# Automotive_Car_Cover_with_anti-theft_ale.net
KiCad netlist of a schematic drawn in EAGLE
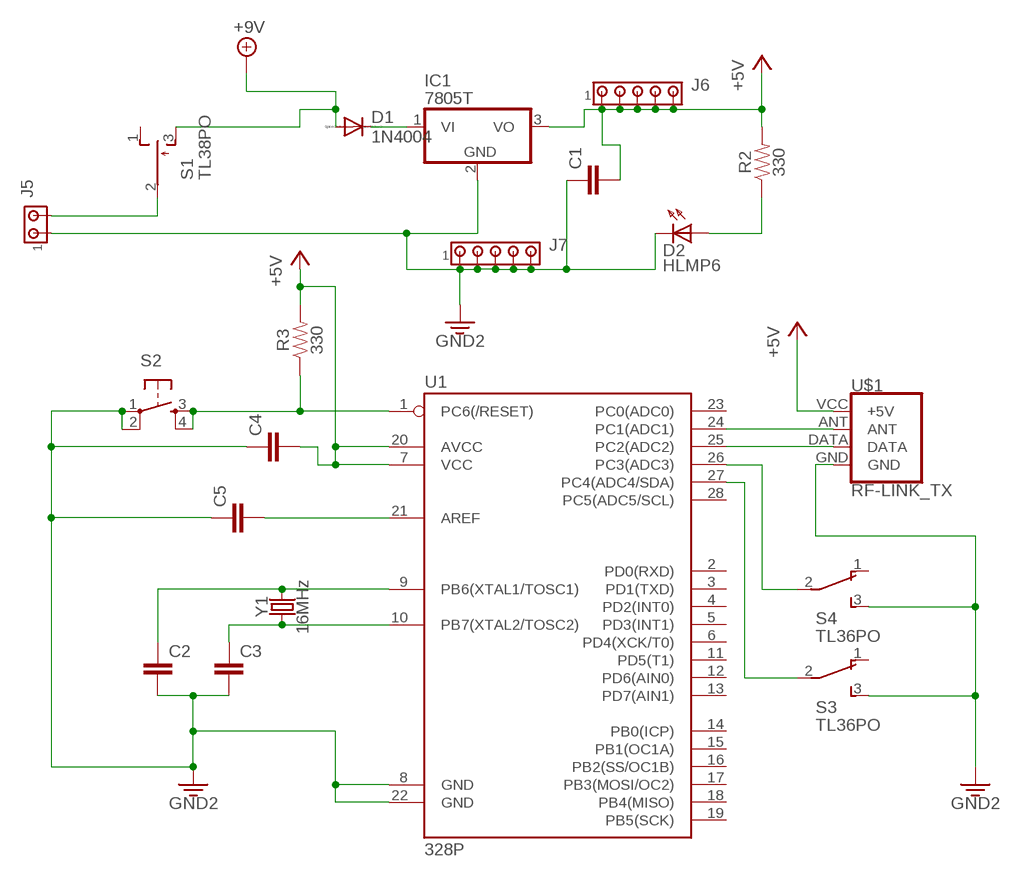
[diagram p0: schematic, sheet 1]

(export (version "E")
  (design (tool "Eeschema 10.0.6"))
  (components
    (comp (ref "C1")
      (value "C5/2.5")
      (footprint "eagle-import:C5B2.5")
      (libsource (lib "eagle-import") (part "C5/2.5"))
    )
    (comp (ref "C2")
      (value "C5/2.5")
      (footprint "eagle-import:C5B2.5")
      (libsource (lib "eagle-import") (part "C5/2.5"))
    )
    (comp (ref "C3")
      (value "C5/2.5")
      (footprint "eagle-import:C5B2.5")
      (libsource (lib "eagle-import") (part "C5/2.5"))
    )
    (comp (ref "C4")
      (value "C5/2.5")
      (footprint "eagle-import:C5B2.5")
      (libsource (lib "eagle-import") (part "C5/2.5"))
    )
    (comp (ref "C5")
      (value "C5/2.5")
      (footprint "eagle-import:C5B2.5")
      (libsource (lib "eagle-import") (part "C5/2.5"))
    )
    (comp (ref "D1")
      (value "1N4004")
      (footprint "eagle-import:DO41-10")
      (libsource (lib "eagle-import") (part "1N4004"))
    )
    (comp (ref "D2")
      (value "HLMP6")
      (footprint "eagle-import:HLMP6")
      (fields (field (name "MF") "AGILENT TECHNOLOGIES") (field (name "MPN") "HLMP-6500"))
      (libsource (lib "eagle-import") (part "HLMP6"))
    )
    (comp (ref "IC1")
      (value "7805T")
      (footprint "eagle-import:TO220H")
      (libsource (lib "eagle-import") (part "78T05"))
    )
    (comp (ref "J5")
      (value "MTA02-156")
      (footprint "eagle-import:1X2MTA")
      (libsource (lib "eagle-import") (part "MTA02-156"))
    )
    (comp (ref "J6")
      (value "MTA05-100")
      (footprint "eagle-import:10X05MTA")
      (libsource (lib "eagle-import") (part "MTA05-100"))
    )
    (comp (ref "J7")
      (value "MTA05-100")
      (footprint "eagle-import:10X05MTA")
      (libsource (lib "eagle-import") (part "MTA05-100"))
    )
    (comp (ref "R2")
      (value "330")
      (footprint "eagle-import:AXIAL-0.3")
      (libsource (lib "eagle-import") (part "330OHM-HORIZ-1/10W-5%"))
    )
    (comp (ref "R3")
      (value "330")
      (footprint "eagle-import:AXIAL-0.3")
      (libsource (lib "eagle-import") (part "330OHM-HORIZ-1/10W-5%"))
    )
    (comp (ref "S1")
      (value "TL38PO")
      (footprint "eagle-import:TL3XPO")
      (libsource (lib "eagle-import") (part "TL38PO"))
    )
    (comp (ref "S2")
      (value "TAC_SWITCHPTH")
      (footprint "eagle-import:TACTILE-PTH")
      (libsource (lib "eagle-import") (part "TAC_SWITCHPTH"))
    )
    (comp (ref "S3")
      (value "TL36PO")
      (footprint "eagle-import:TL3XPO")
      (libsource (lib "eagle-import") (part "TL36PO"))
    )
    (comp (ref "S4")
      (value "TL36PO")
      (footprint "eagle-import:TL3XPO")
      (libsource (lib "eagle-import") (part "TL36PO"))
    )
    (comp (ref "U$1")
      (value "RF-LINK_TX")
      (footprint "eagle-import:RF-LINK_TX")
      (libsource (lib "eagle-import") (part "RF-LINK_TX"))
    )
    (comp (ref "U1")
      (value "328P")
      (footprint "eagle-import:DIP28")
      (libsource (lib "eagle-import") (part "ATMEGA328P_PDIP"))
    )
    (comp (ref "Y1")
      (value "16MHz")
      (footprint "eagle-import:HC49US")
      (libsource (lib "eagle-import") (part "CRYSTAL-16MHZPTH-HC49US"))
    )
  )
  (nets
    (net (code "1") (name "+5V") (class "Default")
      (node (ref "C1") (pin "2") (pinfunction "2_2") (pintype "passive"))
      (node (ref "C4") (pin "2") (pinfunction "2_2") (pintype "passive"))
      (node (ref "IC1") (pin "3") (pinfunction "VO_3") (pintype "passive"))
      (node (ref "J6") (pin "1") (pinfunction "1_1") (pintype "passive"))
      (node (ref "J6") (pin "2") (pinfunction "2_2") (pintype "passive"))
      (node (ref "J6") (pin "3") (pinfunction "3_3") (pintype "passive"))
      (node (ref "J6") (pin "4") (pinfunction "4_4") (pintype "passive"))
      (node (ref "J6") (pin "5") (pinfunction "5_5") (pintype "passive"))
      (node (ref "R2") (pin "P$2") (pinfunction "2_P$2") (pintype "passive"))
      (node (ref "R3") (pin "P$2") (pinfunction "2_P$2") (pintype "passive"))
      (node (ref "U$1") (pin "VCC") (pinfunction "+5V_VCC") (pintype "power_in"))
      (node (ref "U1") (pin "20") (pinfunction "AVCC_20") (pintype "bidirectional"))
      (node (ref "U1") (pin "7") (pinfunction "VCC_7") (pintype "bidirectional"))
    )
    (net (code "2") (name "+9V") (class "Default")
      (node (ref "D1") (pin "A") (pinfunction "A_A") (pintype "passive"))
      (node (ref "S1") (pin "3") (pinfunction "S_3") (pintype "passive"))
    )
    (net (code "3") (name "GND2") (class "Default")
      (node (ref "C1") (pin "1") (pinfunction "1_1") (pintype "passive"))
      (node (ref "C2") (pin "2") (pinfunction "2_2") (pintype "passive"))
      (node (ref "C3") (pin "2") (pinfunction "2_2") (pintype "passive"))
      (node (ref "C4") (pin "1") (pinfunction "1_1") (pintype "passive"))
      (node (ref "C5") (pin "1") (pinfunction "1_1") (pintype "passive"))
      (node (ref "D2") (pin "K") (pinfunction "K_K") (pintype "passive"))
      (node (ref "IC1") (pin "2") (pinfunction "GND_2") (pintype "passive"))
      (node (ref "J5") (pin "1") (pinfunction "1_1") (pintype "passive"))
      (node (ref "J7") (pin "1") (pinfunction "1_1") (pintype "passive"))
      (node (ref "J7") (pin "2") (pinfunction "2_2") (pintype "passive"))
      (node (ref "J7") (pin "3") (pinfunction "3_3") (pintype "passive"))
      (node (ref "J7") (pin "4") (pinfunction "4_4") (pintype "passive"))
      (node (ref "J7") (pin "5") (pinfunction "5_5") (pintype "passive"))
      (node (ref "S2") (pin "1") (pinfunction "1_1") (pintype "passive"))
      (node (ref "S2") (pin "2") (pinfunction "2_2") (pintype "passive"))
      (node (ref "S3") (pin "3") (pinfunction "S_3") (pintype "passive"))
      (node (ref "S4") (pin "3") (pinfunction "S_3") (pintype "passive"))
      (node (ref "U$1") (pin "GND") (pinfunction "GND_GND") (pintype "power_in"))
      (node (ref "U1") (pin "22") (pinfunction "GND_22") (pintype "bidirectional"))
      (node (ref "U1") (pin "8") (pinfunction "GND_8") (pintype "bidirectional"))
    )
    (net (code "4") (name "Net-(IC1-VI)") (class "Default")
      (node (ref "D1") (pin "C") (pinfunction "C_C") (pintype "passive"))
      (node (ref "IC1") (pin "1") (pinfunction "VI_1") (pintype "input"))
    )
    (net (code "5") (name "Net-(R2-1)") (class "Default")
      (node (ref "D2") (pin "A") (pinfunction "A_A") (pintype "passive"))
      (node (ref "R2") (pin "P$1") (pinfunction "1_P$1") (pintype "passive"))
    )
    (net (code "6") (name "Net-(R3-1)") (class "Default")
      (node (ref "R3") (pin "P$1") (pinfunction "1_P$1") (pintype "passive"))
      (node (ref "S2") (pin "3") (pinfunction "3_3") (pintype "passive"))
      (node (ref "S2") (pin "4") (pinfunction "4_4") (pintype "passive"))
      (node (ref "U1") (pin "1") (pinfunction "PC6(/RESET)_1") (pintype "bidirectional"))
    )
    (net (code "7") (name "Net-(S1-P)") (class "Default")
      (node (ref "J5") (pin "2") (pinfunction "2_2") (pintype "passive"))
      (node (ref "S1") (pin "2") (pinfunction "P_2") (pintype "passive"))
    )
    (net (code "8") (name "Net-(S3-P)") (class "Default")
      (node (ref "S3") (pin "2") (pinfunction "P_2") (pintype "passive"))
      (node (ref "U1") (pin "27") (pinfunction "PC4(ADC4/SDA)_27") (pintype "bidirectional"))
    )
    (net (code "9") (name "Net-(S4-P)") (class "Default")
      (node (ref "S4") (pin "2") (pinfunction "P_2") (pintype "passive"))
      (node (ref "U1") (pin "26") (pinfunction "PC3(ADC3)_26") (pintype "bidirectional"))
    )
    (net (code "10") (name "Net-(U1-AREF)") (class "Default")
      (node (ref "C5") (pin "2") (pinfunction "2_2") (pintype "passive"))
      (node (ref "U1") (pin "21") (pinfunction "AREF_21") (pintype "bidirectional"))
    )
    (net (code "11") (name "Net-(U1-PB6(XTAL1{slash}TOSC1))") (class "Default")
      (node (ref "C2") (pin "1") (pinfunction "1_1") (pintype "passive"))
      (node (ref "U1") (pin "9") (pinfunction "PB6(XTAL1/TOSC1)_9") (pintype "bidirectional"))
      (node (ref "Y1") (pin "2") (pinfunction "2_2") (pintype "passive"))
    )
    (net (code "12") (name "Net-(U1-PB7(XTAL2{slash}TOSC2))") (class "Default")
      (node (ref "C3") (pin "1") (pinfunction "1_1") (pintype "passive"))
      (node (ref "U1") (pin "10") (pinfunction "PB7(XTAL2/TOSC2)_10") (pintype "bidirectional"))
      (node (ref "Y1") (pin "1") (pinfunction "1_1") (pintype "passive"))
    )
    (net (code "13") (name "Net-(U1-PC1(ADC1))") (class "Default")
      (node (ref "U$1") (pin "ANT") (pinfunction "ANT_ANT") (pintype "passive"))
      (node (ref "U1") (pin "24") (pinfunction "PC1(ADC1)_24") (pintype "bidirectional"))
    )
    (net (code "14") (name "Net-(U1-PC2(ADC2))") (class "Default")
      (node (ref "U$1") (pin "DATA") (pinfunction "DATA_DATA") (pintype "input"))
      (node (ref "U1") (pin "25") (pinfunction "PC2(ADC2)_25") (pintype "bidirectional"))
    )
    (net (code "15") (name "unconnected-(S1-O-Pad1)") (class "Default")
      (node (ref "S1") (pin "1") (pinfunction "O_1") (pintype "passive"))
    )
    (net (code "16") (name "unconnected-(S3-O-Pad1)") (class "Default")
      (node (ref "S3") (pin "1") (pinfunction "O_1") (pintype "passive"))
    )
    (net (code "17") (name "unconnected-(S4-O-Pad1)") (class "Default")
      (node (ref "S4") (pin "1") (pinfunction "O_1") (pintype "passive"))
    )
    (net (code "18") (name "unconnected-(U1-PB0(ICP)-Pad14)") (class "Default")
      (node (ref "U1") (pin "14") (pinfunction "PB0(ICP)_14") (pintype "bidirectional"))
    )
    (net (code "19") (name "unconnected-(U1-PB1(OC1A)-Pad15)") (class "Default")
      (node (ref "U1") (pin "15") (pinfunction "PB1(OC1A)_15") (pintype "bidirectional"))
    )
    (net (code "20") (name "unconnected-(U1-PB2(SS{slash}OC1B)-Pad16)") (class "Default")
      (node (ref "U1") (pin "16") (pinfunction "PB2(SS/OC1B)_16") (pintype "bidirectional"))
    )
    (net (code "21") (name "unconnected-(U1-PB3(MOSI{slash}OC2)-Pad17)") (class "Default")
      (node (ref "U1") (pin "17") (pinfunction "PB3(MOSI/OC2)_17") (pintype "bidirectional"))
    )
    (net (code "22") (name "unconnected-(U1-PB4(MISO)-Pad18)") (class "Default")
      (node (ref "U1") (pin "18") (pinfunction "PB4(MISO)_18") (pintype "bidirectional"))
    )
    (net (code "23") (name "unconnected-(U1-PB5(SCK)-Pad19)") (class "Default")
      (node (ref "U1") (pin "19") (pinfunction "PB5(SCK)_19") (pintype "bidirectional"))
    )
    (net (code "24") (name "unconnected-(U1-PC0(ADC0)-Pad23)") (class "Default")
      (node (ref "U1") (pin "23") (pinfunction "PC0(ADC0)_23") (pintype "bidirectional"))
    )
    (net (code "25") (name "unconnected-(U1-PC5(ADC5{slash}SCL)-Pad28)") (class "Default")
      (node (ref "U1") (pin "28") (pinfunction "PC5(ADC5/SCL)_28") (pintype "bidirectional"))
    )
    (net (code "26") (name "unconnected-(U1-PD0(RXD)-Pad2)") (class "Default")
      (node (ref "U1") (pin "2") (pinfunction "PD0(RXD)_2") (pintype "bidirectional"))
    )
    (net (code "27") (name "unconnected-(U1-PD1(TXD)-Pad3)") (class "Default")
      (node (ref "U1") (pin "3") (pinfunction "PD1(TXD)_3") (pintype "bidirectional"))
    )
    (net (code "28") (name "unconnected-(U1-PD2(INT0)-Pad4)") (class "Default")
      (node (ref "U1") (pin "4") (pinfunction "PD2(INT0)_4") (pintype "bidirectional"))
    )
    (net (code "29") (name "unconnected-(U1-PD3(INT1)-Pad5)") (class "Default")
      (node (ref "U1") (pin "5") (pinfunction "PD3(INT1)_5") (pintype "bidirectional"))
    )
    (net (code "30") (name "unconnected-(U1-PD4(XCK{slash}T0)-Pad6)") (class "Default")
      (node (ref "U1") (pin "6") (pinfunction "PD4(XCK/T0)_6") (pintype "bidirectional"))
    )
    (net (code "31") (name "unconnected-(U1-PD5(T1)-Pad11)") (class "Default")
      (node (ref "U1") (pin "11") (pinfunction "PD5(T1)_11") (pintype "bidirectional"))
    )
    (net (code "32") (name "unconnected-(U1-PD6(AIN0)-Pad12)") (class "Default")
      (node (ref "U1") (pin "12") (pinfunction "PD6(AIN0)_12") (pintype "bidirectional"))
    )
    (net (code "33") (name "unconnected-(U1-PD7(AIN1)-Pad13)") (class "Default")
      (node (ref "U1") (pin "13") (pinfunction "PD7(AIN1)_13") (pintype "bidirectional"))
    )
  )
)
